# Nixie_2.net
KiCad netlist of a schematic drawn in Altium Designer
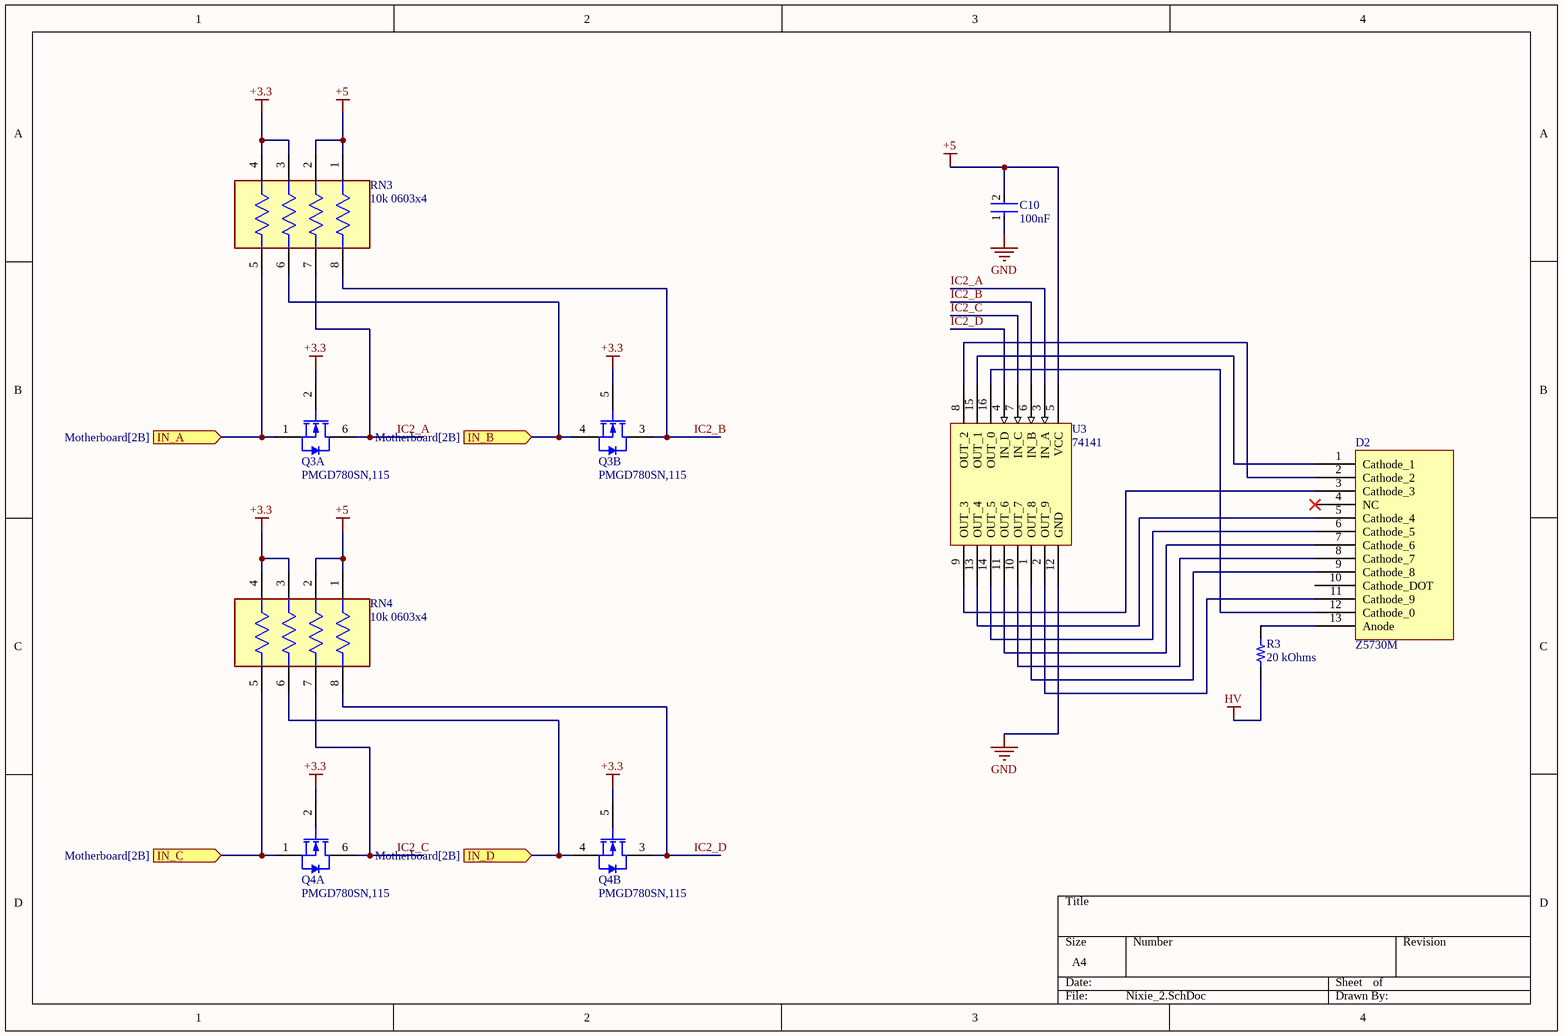
[diagram p0: Nixie_2.SchDoc]

(export (version "E")
  (design (tool "Eeschema 10.0.6"))
  (components
    (comp (ref "C10")
      (value "100nF")
      (footprint "FP-C1005-050-0_15-MFG")
      (description "CAP CER 100nF 10V X5R 0402")
      (fields (field (name "TOLERANCE") "20%") (field (name "VOLTAGE") "10V"))
      (libsource (lib "Altium Content Vault") (part "11868f565c42a9108669ba33697ecf6"))
    )
    (comp (ref "D2") (value "Z5730M") (footprint "Z5730M") (libsource (lib "Z5730M") (part "Z5730M")))
    (comp (ref "Q3")
      (value "PMGD780SN,115")
      (footprint "NXP-SOT363_N")
      (description "Dual N-Channel uTrenchMOS Standard Level FET, 60 V, 0.49 A, 6-Pin SOT363, Tape and Reel")
      (fields (field (name "MANUFACTURER") "NXP Semiconductors"))
      (libsource (lib "Altium Content Vault") (part "NXP-NNMOS-SGDSGD-6_B"))
    )
    (comp (ref "Q4")
      (value "PMGD780SN,115")
      (footprint "NXP-SOT363_N")
      (description "Dual N-Channel uTrenchMOS Standard Level FET, 60 V, 0.49 A, 6-Pin SOT363, Tape and Reel")
      (fields (field (name "MANUFACTURER") "NXP Semiconductors"))
      (libsource (lib "Altium Content Vault") (part "NXP-NNMOS-SGDSGD-6_B"))
    )
    (comp (ref "R3")
      (value "20 kOhms")
      (footprint "RES 1210_3225")
      (description "RES SMD 20K OHM 1% 3/4W 1210")
      (fields (field (name "PART NUMBER") "CRCW121020K0FKEAHP") (field (name "MANUFACTURER") "Vishay Dale"))
      (libsource (lib "Celestial Altium Library - altium_library") (part "Resistor"))
    )
    (comp (ref "RN3")
      (value "10k 0603x4")
      (footprint "FP-EXB38V-MFG")
      (description "RES ARRAY 4 RES 10K OHM 1206\r\nRC-ML08W103JT")
      (fields (field (name "TOLERANCE") "5%"))
      (libsource (lib "Altium Content Vault") (part "2ca08171d0bbdee8be62227dae509d7"))
    )
    (comp (ref "RN4")
      (value "10k 0603x4")
      (footprint "FP-EXB38V-MFG")
      (description "RES ARRAY 4 RES 10K OHM 1206\r\nRC-ML08W103JT")
      (fields (field (name "TOLERANCE") "5%"))
      (libsource (lib "Altium Content Vault") (part "2ca08171d0bbdee8be62227dae509d7"))
    )
    (comp (ref "U3") (value "74141") (footprint "DIP-16") (libsource (lib "Z5730M") (part "74141")))
  )
  (nets
    (net (code "1") (name "+3.3") (class "Default")
      (node (ref "Q3") (pin "2") (pinfunction "G1_2") (pintype "passive"))
      (node (ref "Q3") (pin "5") (pinfunction "G2_5") (pintype "passive"))
      (node (ref "Q4") (pin "2") (pinfunction "G1_2") (pintype "passive"))
      (node (ref "Q4") (pin "5") (pinfunction "G2_5") (pintype "passive"))
      (node (ref "RN3") (pin "3") (pinfunction "3_3") (pintype "passive"))
      (node (ref "RN3") (pin "4") (pinfunction "4_4") (pintype "passive"))
      (node (ref "RN4") (pin "3") (pinfunction "3_3") (pintype "passive"))
      (node (ref "RN4") (pin "4") (pinfunction "4_4") (pintype "passive"))
    )
    (net (code "2") (name "+5") (class "Default")
      (node (ref "C10") (pin "2") (pinfunction "2_2") (pintype "passive"))
      (node (ref "RN3") (pin "1") (pinfunction "1_1") (pintype "passive"))
      (node (ref "RN3") (pin "2") (pinfunction "2_2") (pintype "passive"))
      (node (ref "RN4") (pin "1") (pinfunction "1_1") (pintype "passive"))
      (node (ref "RN4") (pin "2") (pinfunction "2_2") (pintype "passive"))
      (node (ref "U3") (pin "5") (pinfunction "VCC_5") (pintype "power_in"))
    )
    (net (code "3") (name "/IC2_A") (class "Default")
      (node (ref "Q3") (pin "6") (pinfunction "D1_6") (pintype "passive"))
      (node (ref "RN3") (pin "7") (pinfunction "7_7") (pintype "passive"))
      (node (ref "U3") (pin "3") (pinfunction "IN_A_3") (pintype "input"))
    )
    (net (code "4") (name "/IC2_B") (class "Default")
      (node (ref "Q3") (pin "3") (pinfunction "D2_3") (pintype "passive"))
      (node (ref "RN3") (pin "8") (pinfunction "8_8") (pintype "passive"))
      (node (ref "U3") (pin "6") (pinfunction "IN_B_6") (pintype "input"))
    )
    (net (code "5") (name "/IC2_C") (class "Default")
      (node (ref "Q4") (pin "6") (pinfunction "D1_6") (pintype "passive"))
      (node (ref "RN4") (pin "7") (pinfunction "7_7") (pintype "passive"))
      (node (ref "U3") (pin "7") (pinfunction "IN_C_7") (pintype "input"))
    )
    (net (code "6") (name "/IC2_D") (class "Default")
      (node (ref "Q4") (pin "3") (pinfunction "D2_3") (pintype "passive"))
      (node (ref "RN4") (pin "8") (pinfunction "8_8") (pintype "passive"))
      (node (ref "U3") (pin "4") (pinfunction "IN_D_4") (pintype "input"))
    )
    (net (code "7") (name "/IN_A") (class "Default")
      (node (ref "Q3") (pin "1") (pinfunction "S1_1") (pintype "passive"))
      (node (ref "RN3") (pin "5") (pinfunction "5_5") (pintype "passive"))
    )
    (net (code "8") (name "/IN_B") (class "Default")
      (node (ref "Q3") (pin "4") (pinfunction "S2_4") (pintype "passive"))
      (node (ref "RN3") (pin "6") (pinfunction "6_6") (pintype "passive"))
    )
    (net (code "9") (name "/IN_C") (class "Default")
      (node (ref "Q4") (pin "1") (pinfunction "S1_1") (pintype "passive"))
      (node (ref "RN4") (pin "5") (pinfunction "5_5") (pintype "passive"))
    )
    (net (code "10") (name "/IN_D") (class "Default")
      (node (ref "Q4") (pin "4") (pinfunction "S2_4") (pintype "passive"))
      (node (ref "RN4") (pin "6") (pinfunction "6_6") (pintype "passive"))
    )
    (net (code "11") (name "GND") (class "Default")
      (node (ref "C10") (pin "1") (pinfunction "1_1") (pintype "passive"))
      (node (ref "U3") (pin "12") (pinfunction "GND_12") (pintype "power_in"))
    )
    (net (code "12") (name "HV") (class "Default")
      (node (ref "R3") (pin "1") (pinfunction "1_1") (pintype "passive"))
    )
    (net (code "13") (name "Net-(D2-Anode)") (class "Default")
      (node (ref "D2") (pin "13") (pinfunction "Anode_13") (pintype "passive"))
      (node (ref "R3") (pin "2") (pinfunction "2_2") (pintype "passive"))
    )
    (net (code "14") (name "Net-(D2-Cathode_0)") (class "Default")
      (node (ref "D2") (pin "12") (pinfunction "Cathode_0_12") (pintype "passive"))
      (node (ref "U3") (pin "16") (pinfunction "OUT_0_16") (pintype "open_collector"))
    )
    (net (code "15") (name "Net-(D2-Cathode_1)") (class "Default")
      (node (ref "D2") (pin "1") (pinfunction "Cathode_1_1") (pintype "passive"))
      (node (ref "U3") (pin "15") (pinfunction "OUT_1_15") (pintype "open_collector"))
    )
    (net (code "16") (name "Net-(D2-Cathode_2)") (class "Default")
      (node (ref "D2") (pin "2") (pinfunction "Cathode_2_2") (pintype "passive"))
      (node (ref "U3") (pin "8") (pinfunction "OUT_2_8") (pintype "open_collector"))
    )
    (net (code "17") (name "Net-(D2-Cathode_3)") (class "Default")
      (node (ref "D2") (pin "3") (pinfunction "Cathode_3_3") (pintype "passive"))
      (node (ref "U3") (pin "9") (pinfunction "OUT_3_9") (pintype "open_collector"))
    )
    (net (code "18") (name "Net-(D2-Cathode_4)") (class "Default")
      (node (ref "D2") (pin "5") (pinfunction "Cathode_4_5") (pintype "passive"))
      (node (ref "U3") (pin "13") (pinfunction "OUT_4_13") (pintype "open_collector"))
    )
    (net (code "19") (name "Net-(D2-Cathode_5)") (class "Default")
      (node (ref "D2") (pin "6") (pinfunction "Cathode_5_6") (pintype "passive"))
      (node (ref "U3") (pin "14") (pinfunction "OUT_5_14") (pintype "open_collector"))
    )
    (net (code "20") (name "Net-(D2-Cathode_6)") (class "Default")
      (node (ref "D2") (pin "7") (pinfunction "Cathode_6_7") (pintype "passive"))
      (node (ref "U3") (pin "11") (pinfunction "OUT_6_11") (pintype "open_collector"))
    )
    (net (code "21") (name "Net-(D2-Cathode_7)") (class "Default")
      (node (ref "D2") (pin "8") (pinfunction "Cathode_7_8") (pintype "passive"))
      (node (ref "U3") (pin "10") (pinfunction "OUT_7_10") (pintype "open_collector"))
    )
    (net (code "22") (name "Net-(D2-Cathode_8)") (class "Default")
      (node (ref "D2") (pin "9") (pinfunction "Cathode_8_9") (pintype "passive"))
      (node (ref "U3") (pin "1") (pinfunction "OUT_8_1") (pintype "open_collector"))
    )
    (net (code "23") (name "Net-(D2-Cathode_9)") (class "Default")
      (node (ref "D2") (pin "11") (pinfunction "Cathode_9_11") (pintype "passive"))
      (node (ref "U3") (pin "2") (pinfunction "OUT_9_2") (pintype "open_collector"))
    )
    (net (code "24") (name "unconnected-(D2-Cathode_DOT-Pad10)") (class "Default")
      (node (ref "D2") (pin "10") (pinfunction "Cathode_DOT_10") (pintype "passive"))
    )
    (net (code "25") (name "unconnected-(D2-NC-Pad4)") (class "Default")
      (node (ref "D2") (pin "4") (pinfunction "NC_4") (pintype "passive+no_connect"))
    )
  )
)
